# SPEAKER.net
KiCad netlist of a schematic drawn in Altium Designer
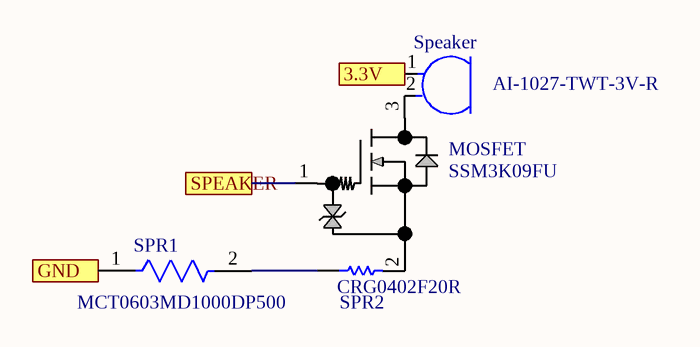
[diagram p0: SPEAKER.SchDoc]

(export (version "E")
  (design (tool "Eeschema 10.0.6"))
  (components
    (comp (ref "MOSFET")
      (value "SSM3K09FU")
      (footprint "USM_TOS")
      (description "No Description Available")
      (fields (field (name "COPYRIGHT") "Copyright (C) 2018 Accelerated Designs. All rights reserved"))
      (libsource (lib "2021-03-01_16-54-40") (part "SSM3K09FU"))
    )
    (comp (ref "Speaker")
      (value "AI-1027-TWT-3V-R")
      (footprint "FP-MA300D1-1-MFG")
      (description "Audio Indicators & Alerts 1300pF 300kHz Ultrasonic Sensor")
      (libsource (lib "Altium Content Vault") (part "1b72337432ad8929c0ae54f99eb68d9"))
    )
    (comp (ref "SPR1")
      (value "MCT0603MD1000DP500")
      (footprint "FP-MCT0603-MFG")
      (description "RES SMD 100 OHM 1% 1/8W 0603")
      (fields (field (name "TOLERANCE") "0.5%"))
      (libsource (lib "Altium Content Vault") (part "1029c3af85768c4190bb7ad29bc67b5"))
    )
    (comp (ref "SPR2")
      (value "CRG0402F20R")
      (footprint "RESC1005X40X25NL10T10")
      (fields (field (name "MANUFACTURER") "TE Connectivity / AMP"))
      (libsource (lib "Altium Content Vault") (part "RES"))
    )
  )
  (nets
    (net (code "1") (name "/3.3V") (class "Default")
      (node (ref "Speaker") (pin "1") (pinfunction "1_1") (pintype "passive"))
    )
    (net (code "2") (name "/GND") (class "Default")
      (node (ref "SPR1") (pin "1") (pinfunction "1_1") (pintype "passive"))
    )
    (net (code "3") (name "/SPEAKER") (class "Default")
      (node (ref "MOSFET") (pin "1") (pinfunction "1_1") (pintype "passive"))
    )
    (net (code "4") (name "Net-(MOSFET-Pad2)") (class "Default")
      (node (ref "MOSFET") (pin "2") (pinfunction "2_2") (pintype "passive"))
      (node (ref "SPR2") (pin "2") (pinfunction "2_2") (pintype "passive"))
    )
    (net (code "5") (name "Net-(MOSFET-Pad3)") (class "Default")
      (node (ref "MOSFET") (pin "3") (pinfunction "3_3") (pintype "passive"))
      (node (ref "Speaker") (pin "2") (pinfunction "2_2") (pintype "passive"))
    )
    (net (code "6") (name "Net-(SPR1-Pad2)") (class "Default")
      (node (ref "SPR1") (pin "2") (pinfunction "2_2") (pintype "passive"))
      (node (ref "SPR2") (pin "1") (pinfunction "1_1") (pintype "passive"))
    )
  )
)
